# Vapeix_eeprom_test.net
KiCad netlist of a schematic drawn in Altium Designer
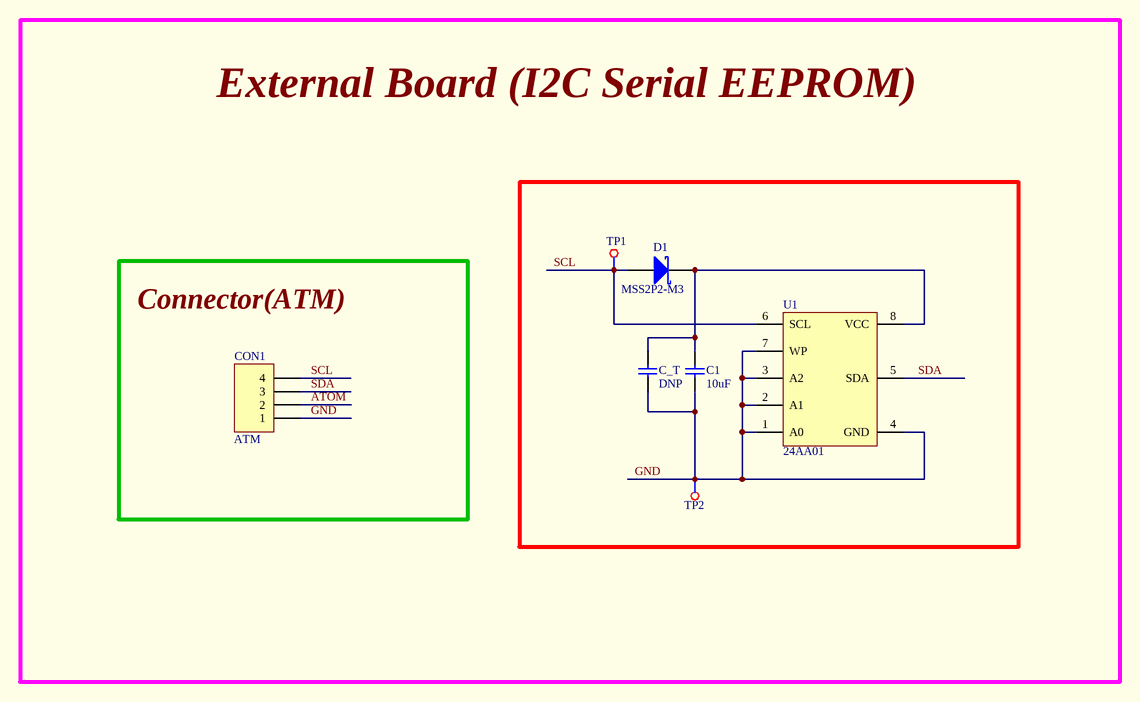
[diagram p0: Vapeix_eeprom_test.SchDoc]

(export (version "E")
  (design (tool "Eeschema 10.0.6"))
  (components
    (comp (ref "C1")
      (value "10uF")
      (footprint "C0402")
      (description "Capacitor, NP0, ±2%")
      (fields (field (name "PART NUMBER") "C0402-12p") (field (name "PUBLISHER") "Nordic Semiconductor"))
      (libsource (lib "Nordic Passive DB") (part "CAP"))
    )
    (comp (ref "CON1")
      (value "ATM")
      (footprint "S4B-PH-K-S")
      (description "CONN HEADER PH SIDE 4POS 2MM")
      (fields
        (field (name "MANUFACTURER") "JST Sales America Inc.")
        (field (name "MANUFACTURER PART NUMBER") "S4B-PH-K-S(LF)(SN)")
      )
      (libsource (lib "VapeixS_LIB") (part "S4B-PH-K-S(LF)(SN)"))
    )
    (comp (ref "C_T")
      (value "DNP")
      (footprint "C0201")
      (description "Capacitor, NP0, ±2%")
      (fields (field (name "PART NUMBER") "C0402-12p") (field (name "PUBLISHER") "Nordic Semiconductor"))
      (libsource (lib "Nordic Passive DB") (part "CAP"))
    )
    (comp (ref "D1")
      (value "MSS2P2-M3")
      (footprint "MSS2P2-M3")
      (description "DIODE SCHOTTKY 20V 2A MICROSMP")
      (fields
        (field (name "MANUFACTURER") "Vishay Semiconductor Diodes Division")
        (field (name "MANUFACTURER PART NUMBER") "MSS2P2-M3/89A")
      )
      (libsource (lib "VapeixS_LIB") (part "MSS2P2-M3/89A"))
    )
    (comp (ref "TP1")
      (value "TP")
      (footprint "TP")
      (description "TEST POINT")
      (libsource (lib "VapeixS_LIB") (part "TP"))
    )
    (comp (ref "TP2")
      (value "TP")
      (footprint "TP")
      (description "TEST POINT")
      (libsource (lib "") (part "TP_1"))
    )
    (comp (ref "U1")
      (value "24AA01")
      (footprint "24AA01")
      (description "IC EEPROM 1KBIT 400KHZ 8SOIC")
      (fields
        (field (name "MANUFACTURER") "Microchip Technology")
        (field (name "MANUFACTURER PART NUMBER") "24AA01-I/SN")
      )
      (libsource (lib "ExternalLib") (part "24AA01-I/SN"))
    )
  )
  (nets
    (net (code "1") (name "/ATOM") (class "Default")
      (node (ref "CON1") (pin "2") (pinfunction "2_2") (pintype "passive"))
    )
    (net (code "4") (name "/GND") (class "Default")
      (node (ref "C1") (pin "1") (pinfunction "1_1") (pintype "passive"))
      (node (ref "CON1") (pin "1") (pinfunction "1_1") (pintype "passive"))
      (node (ref "C_T") (pin "1") (pinfunction "1_1") (pintype "passive"))
      (node (ref "TP2") (pin "1") (pinfunction "TP_1") (pintype "passive"))
      (node (ref "U1") (pin "1") (pinfunction "A0_1") (pintype "passive"))
      (node (ref "U1") (pin "2") (pinfunction "A1_2") (pintype "passive"))
      (node (ref "U1") (pin "3") (pinfunction "A2_3") (pintype "passive"))
      (node (ref "U1") (pin "4") (pinfunction "GND_4") (pintype "passive"))
      (node (ref "U1") (pin "7") (pinfunction "WP_7") (pintype "passive"))
    )
    (net (code "5") (name "/SCL") (class "Default")
      (node (ref "CON1") (pin "4") (pinfunction "4_4") (pintype "passive"))
      (node (ref "D1") (pin "1") (pinfunction "A_1") (pintype "passive"))
      (node (ref "TP1") (pin "1") (pinfunction "TP_1") (pintype "passive"))
      (node (ref "U1") (pin "6") (pinfunction "SCL_6") (pintype "passive"))
    )
    (net (code "6") (name "/SDA") (class "Default")
      (node (ref "CON1") (pin "3") (pinfunction "3_3") (pintype "passive"))
      (node (ref "U1") (pin "5") (pinfunction "SDA_5") (pintype "passive"))
    )
    (net (code "7") (name "Net-(D1-K)") (class "Default")
      (node (ref "C1") (pin "2") (pinfunction "2_2") (pintype "passive"))
      (node (ref "C_T") (pin "2") (pinfunction "2_2") (pintype "passive"))
      (node (ref "D1") (pin "2") (pinfunction "K_2") (pintype "passive"))
      (node (ref "U1") (pin "8") (pinfunction "VCC_8") (pintype "passive"))
    )
  )
)
